# design.net
KiCad netlist of a schematic drawn in Altium Designer
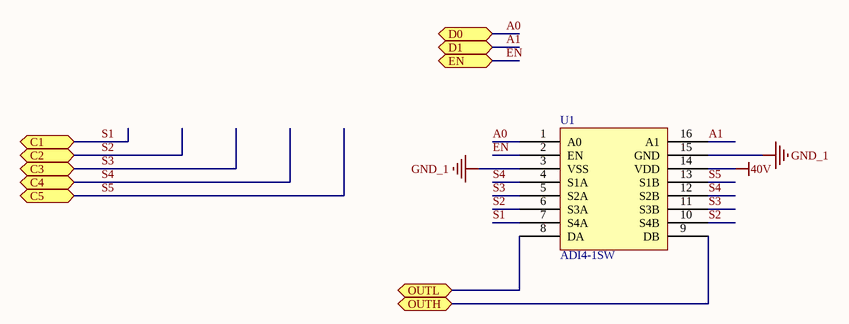
[diagram p0: 模拟开关.SchDoc]

(export (version "E")
  (design (tool "Eeschema 10.0.6"))
  (components
    (comp (ref "U1") (value "ADI4-1SW") (footprint "TSSOP16") (libsource (lib "ic_lib") (part "ADI4-1SW")))
  )
  (nets
    (net (code "1") (name "/A0") (class "Default")
      (node (ref "U1") (pin "1") (pinfunction "A0_1") (pintype "passive"))
    )
    (net (code "2") (name "/A1") (class "Default")
      (node (ref "U1") (pin "16") (pinfunction "A1_16") (pintype "passive"))
    )
    (net (code "3") (name "/EN") (class "Default")
      (node (ref "U1") (pin "2") (pinfunction "EN_2") (pintype "passive"))
    )
    (net (code "4") (name "/OUTH") (class "Default")
      (node (ref "U1") (pin "9") (pinfunction "DB_9") (pintype "passive"))
    )
    (net (code "5") (name "/OUTL") (class "Default")
      (node (ref "U1") (pin "8") (pinfunction "DA_8") (pintype "passive"))
    )
    (net (code "6") (name "/S1") (class "Default")
      (node (ref "U1") (pin "7") (pinfunction "S4A_7") (pintype "passive"))
    )
    (net (code "7") (name "/S2") (class "Default")
      (node (ref "U1") (pin "10") (pinfunction "S4B_10") (pintype "passive"))
      (node (ref "U1") (pin "6") (pinfunction "S3A_6") (pintype "passive"))
    )
    (net (code "8") (name "/S3") (class "Default")
      (node (ref "U1") (pin "11") (pinfunction "S3B_11") (pintype "passive"))
      (node (ref "U1") (pin "5") (pinfunction "S2A_5") (pintype "passive"))
    )
    (net (code "9") (name "/S4") (class "Default")
      (node (ref "U1") (pin "12") (pinfunction "S2B_12") (pintype "passive"))
      (node (ref "U1") (pin "4") (pinfunction "S1A_4") (pintype "passive"))
    )
    (net (code "10") (name "/S5") (class "Default")
      (node (ref "U1") (pin "13") (pinfunction "S1B_13") (pintype "passive"))
    )
    (net (code "11") (name "40V") (class "Default")
      (node (ref "U1") (pin "14") (pinfunction "VDD_14") (pintype "passive"))
    )
    (net (code "12") (name "GND_1") (class "Default")
      (node (ref "U1") (pin "15") (pinfunction "GND_15") (pintype "passive"))
      (node (ref "U1") (pin "3") (pinfunction "VSS_3") (pintype "passive"))
    )
  )
)
